# MCU_power_input.net
KiCad netlist of a schematic drawn in Altium Designer
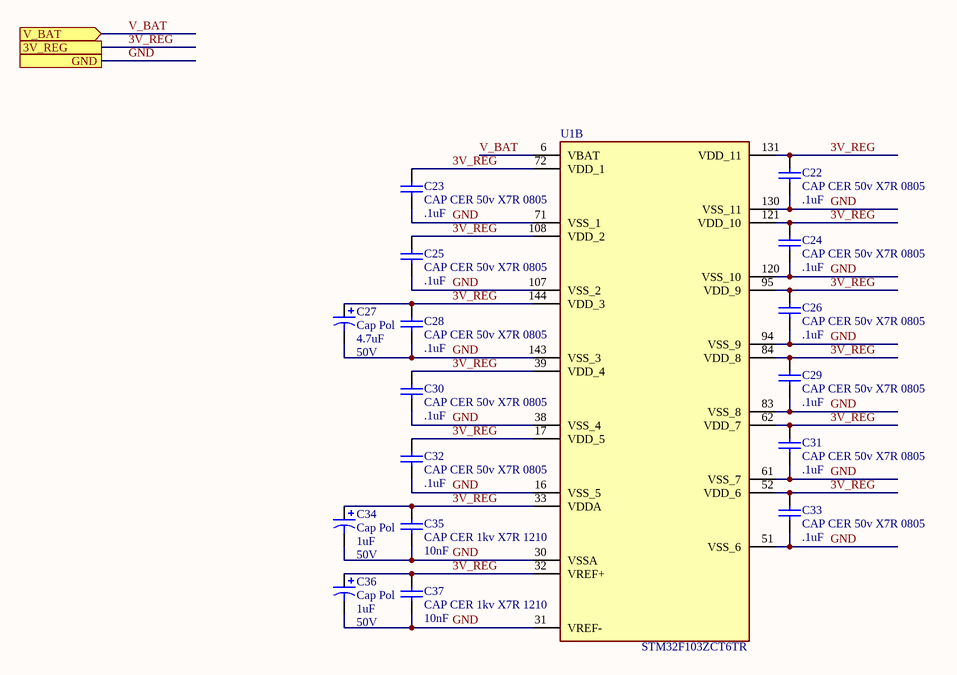
[diagram p0: MCU_power_input.SchDoc]

(export (version "E")
  (design (tool "Eeschema 10.0.6"))
  (components
    (comp (ref "C22")
      (value "CAP CER 50v X7R 0805")
      (footprint "CAPC2012X09M")
      (fields
        (field (name "ALTIUM_VALUE") ".1uF")
        (field (name "TOLERANCE") "±5%")
        (field (name "MPN") "C0805C104J5RACTU")
      )
      (libsource (lib "esd_library") (part "CAP-X7R-.1uF-50V-±5%"))
    )
    (comp (ref "C23")
      (value "CAP CER 50v X7R 0805")
      (footprint "CAPC2012X09M")
      (fields
        (field (name "ALTIUM_VALUE") ".1uF")
        (field (name "TOLERANCE") "±5%")
        (field (name "MPN") "C0805C104J5RACTU")
      )
      (libsource (lib "esd_library") (part "CAP-X7R-.1uF-50V-±5%"))
    )
    (comp (ref "C24")
      (value "CAP CER 50v X7R 0805")
      (footprint "CAPC2012X09M")
      (fields
        (field (name "ALTIUM_VALUE") ".1uF")
        (field (name "TOLERANCE") "±5%")
        (field (name "MPN") "C0805C104J5RACTU")
      )
      (libsource (lib "esd_library") (part "CAP-X7R-.1uF-50V-±5%"))
    )
    (comp (ref "C25")
      (value "CAP CER 50v X7R 0805")
      (footprint "CAPC2012X09M")
      (fields
        (field (name "ALTIUM_VALUE") ".1uF")
        (field (name "TOLERANCE") "±5%")
        (field (name "MPN") "C0805C104J5RACTU")
      )
      (libsource (lib "esd_library") (part "CAP-X7R-.1uF-50V-±5%"))
    )
    (comp (ref "C26")
      (value "CAP CER 50v X7R 0805")
      (footprint "CAPC2012X09M")
      (fields
        (field (name "ALTIUM_VALUE") ".1uF")
        (field (name "TOLERANCE") "±5%")
        (field (name "MPN") "C0805C104J5RACTU")
      )
      (libsource (lib "esd_library") (part "CAP-X7R-.1uF-50V-±5%"))
    )
    (comp (ref "C27")
      (value "Cap Pol")
      (footprint "CAPACITOR_5MM")
      (description "CAP 85C 4.7uF ±20% 50V WX Series Aluminum Electrolytic")
      (fields
        (field (name "ALTIUM_VALUE") "4.7uF")
        (field (name "VOLTAGE") "50V")
        (field (name "MPN") "UWX1H4R7MCL1GB")
      )
      (libsource (lib "esd_library") (part "Cap Polar-4.7uF-50V"))
    )
    (comp (ref "C28")
      (value "CAP CER 50v X7R 0805")
      (footprint "CAPC2012X09M")
      (fields
        (field (name "ALTIUM_VALUE") ".1uF")
        (field (name "TOLERANCE") "±5%")
        (field (name "MPN") "C0805C104J5RACTU")
      )
      (libsource (lib "esd_library") (part "CAP-X7R-.1uF-50V-±5%"))
    )
    (comp (ref "C29")
      (value "CAP CER 50v X7R 0805")
      (footprint "CAPC2012X09M")
      (fields
        (field (name "ALTIUM_VALUE") ".1uF")
        (field (name "TOLERANCE") "±5%")
        (field (name "MPN") "C0805C104J5RACTU")
      )
      (libsource (lib "esd_library") (part "CAP-X7R-.1uF-50V-±5%"))
    )
    (comp (ref "C30")
      (value "CAP CER 50v X7R 0805")
      (footprint "CAPC2012X09M")
      (fields
        (field (name "ALTIUM_VALUE") ".1uF")
        (field (name "TOLERANCE") "±5%")
        (field (name "MPN") "C0805C104J5RACTU")
      )
      (libsource (lib "esd_library") (part "CAP-X7R-.1uF-50V-±5%"))
    )
    (comp (ref "C31")
      (value "CAP CER 50v X7R 0805")
      (footprint "CAPC2012X09M")
      (fields
        (field (name "ALTIUM_VALUE") ".1uF")
        (field (name "TOLERANCE") "±5%")
        (field (name "MPN") "C0805C104J5RACTU")
      )
      (libsource (lib "esd_library") (part "CAP-X7R-.1uF-50V-±5%"))
    )
    (comp (ref "C32")
      (value "CAP CER 50v X7R 0805")
      (footprint "CAPC2012X09M")
      (fields
        (field (name "ALTIUM_VALUE") ".1uF")
        (field (name "TOLERANCE") "±5%")
        (field (name "MPN") "C0805C104J5RACTU")
      )
      (libsource (lib "esd_library") (part "CAP-X7R-.1uF-50V-±5%"))
    )
    (comp (ref "C33")
      (value "CAP CER 50v X7R 0805")
      (footprint "CAPC2012X09M")
      (fields
        (field (name "ALTIUM_VALUE") ".1uF")
        (field (name "TOLERANCE") "±5%")
        (field (name "MPN") "C0805C104J5RACTU")
      )
      (libsource (lib "esd_library") (part "CAP-X7R-.1uF-50V-±5%"))
    )
    (comp (ref "C34")
      (value "Cap Pol")
      (footprint "CAPACITOR_3MM")
      (description "CAP 85C 1uF ±20% 50V WX Series Aluminum Electrolytic")
      (fields
        (field (name "ALTIUM_VALUE") "1uF")
        (field (name "VOLTAGE") "50V")
        (field (name "MPN") "UWX1H010MCL2GB")
      )
      (libsource (lib "esd_library") (part "Cap Polar-1uF-50V"))
    )
    (comp (ref "C35")
      (value "CAP CER 1kv X7R 1210")
      (footprint "CAPC3225X25M")
      (fields
        (field (name "ALTIUM_VALUE") "10nF")
        (field (name "TOLERANCE") "±5%")
        (field (name "MPN") "C1210C103JDRACTU")
      )
      (libsource (lib "esd_library") (part "CAP-X7R-10000pF-1000V-±5%"))
    )
    (comp (ref "C36")
      (value "Cap Pol")
      (footprint "CAPACITOR_3MM")
      (description "CAP 85C 1uF ±20% 50V WX Series Aluminum Electrolytic")
      (fields
        (field (name "ALTIUM_VALUE") "1uF")
        (field (name "VOLTAGE") "50V")
        (field (name "MPN") "UWX1H010MCL2GB")
      )
      (libsource (lib "esd_library") (part "Cap Polar-1uF-50V"))
    )
    (comp (ref "C37")
      (value "CAP CER 1kv X7R 1210")
      (footprint "CAPC3225X25M")
      (fields
        (field (name "ALTIUM_VALUE") "10nF")
        (field (name "TOLERANCE") "±5%")
        (field (name "MPN") "C1210C103JDRACTU")
      )
      (libsource (lib "esd_library") (part "CAP-X7R-10000pF-1000V-±5%"))
    )
    (comp (ref "U1")
      (value "STM32F103ZCT6TR")
      (footprint "QFP50P2200X2200X160-144N")
      (fields (field (name "DIGI-KEY_PART_NUMBER") "497-18761-2-ND") (field (name "MF") "STMicroelectronics"))
      (libsource (lib "STM32F103ZCT6TR") (part "STM32F103ZCT6TR"))
    )
  )
  (nets
    (net (code "1") (name "/3V_REG") (class "Default")
      (node (ref "C22") (pin "2") (pinfunction "2_2") (pintype "passive"))
      (node (ref "C23") (pin "2") (pinfunction "2_2") (pintype "passive"))
      (node (ref "C24") (pin "2") (pinfunction "2_2") (pintype "passive"))
      (node (ref "C25") (pin "2") (pinfunction "2_2") (pintype "passive"))
      (node (ref "C26") (pin "2") (pinfunction "2_2") (pintype "passive"))
      (node (ref "C27") (pin "1") (pinfunction "1_1") (pintype "passive"))
      (node (ref "C28") (pin "2") (pinfunction "2_2") (pintype "passive"))
      (node (ref "C29") (pin "2") (pinfunction "2_2") (pintype "passive"))
      (node (ref "C30") (pin "2") (pinfunction "2_2") (pintype "passive"))
      (node (ref "C31") (pin "2") (pinfunction "2_2") (pintype "passive"))
      (node (ref "C32") (pin "2") (pinfunction "2_2") (pintype "passive"))
      (node (ref "C33") (pin "2") (pinfunction "2_2") (pintype "passive"))
      (node (ref "C34") (pin "1") (pinfunction "1_1") (pintype "passive"))
      (node (ref "C35") (pin "2") (pinfunction "2_2") (pintype "passive"))
      (node (ref "C36") (pin "1") (pinfunction "1_1") (pintype "passive"))
      (node (ref "C37") (pin "2") (pinfunction "2_2") (pintype "passive"))
      (node (ref "U1") (pin "108") (pinfunction "VDD_2_108") (pintype "power_in"))
      (node (ref "U1") (pin "121") (pinfunction "VDD_10_121") (pintype "power_in"))
      (node (ref "U1") (pin "131") (pinfunction "VDD_11_131") (pintype "power_in"))
      (node (ref "U1") (pin "144") (pinfunction "VDD_3_144") (pintype "power_in"))
      (node (ref "U1") (pin "17") (pinfunction "VDD_5_17") (pintype "power_in"))
      (node (ref "U1") (pin "32") (pinfunction "VREF+_32") (pintype "power_in"))
      (node (ref "U1") (pin "33") (pinfunction "VDDA_33") (pintype "power_in"))
      (node (ref "U1") (pin "39") (pinfunction "VDD_4_39") (pintype "power_in"))
      (node (ref "U1") (pin "52") (pinfunction "VDD_6_52") (pintype "power_in"))
      (node (ref "U1") (pin "62") (pinfunction "VDD_7_62") (pintype "power_in"))
      (node (ref "U1") (pin "72") (pinfunction "VDD_1_72") (pintype "power_in"))
      (node (ref "U1") (pin "84") (pinfunction "VDD_8_84") (pintype "power_in"))
      (node (ref "U1") (pin "95") (pinfunction "VDD_9_95") (pintype "power_in"))
    )
    (net (code "2") (name "/GND") (class "Default")
      (node (ref "C22") (pin "1") (pinfunction "1_1") (pintype "passive"))
      (node (ref "C23") (pin "1") (pinfunction "1_1") (pintype "passive"))
      (node (ref "C24") (pin "1") (pinfunction "1_1") (pintype "passive"))
      (node (ref "C25") (pin "1") (pinfunction "1_1") (pintype "passive"))
      (node (ref "C26") (pin "1") (pinfunction "1_1") (pintype "passive"))
      (node (ref "C27") (pin "2") (pinfunction "2_2") (pintype "passive"))
      (node (ref "C28") (pin "1") (pinfunction "1_1") (pintype "passive"))
      (node (ref "C29") (pin "1") (pinfunction "1_1") (pintype "passive"))
      (node (ref "C30") (pin "1") (pinfunction "1_1") (pintype "passive"))
      (node (ref "C31") (pin "1") (pinfunction "1_1") (pintype "passive"))
      (node (ref "C32") (pin "1") (pinfunction "1_1") (pintype "passive"))
      (node (ref "C33") (pin "1") (pinfunction "1_1") (pintype "passive"))
      (node (ref "C34") (pin "2") (pinfunction "2_2") (pintype "passive"))
      (node (ref "C35") (pin "1") (pinfunction "1_1") (pintype "passive"))
      (node (ref "C36") (pin "2") (pinfunction "2_2") (pintype "passive"))
      (node (ref "C37") (pin "1") (pinfunction "1_1") (pintype "passive"))
      (node (ref "U1") (pin "107") (pinfunction "VSS_2_107") (pintype "power_in"))
      (node (ref "U1") (pin "120") (pinfunction "VSS_10_120") (pintype "power_in"))
      (node (ref "U1") (pin "130") (pinfunction "VSS_11_130") (pintype "power_in"))
      (node (ref "U1") (pin "143") (pinfunction "VSS_3_143") (pintype "power_in"))
      (node (ref "U1") (pin "16") (pinfunction "VSS_5_16") (pintype "power_in"))
      (node (ref "U1") (pin "30") (pinfunction "VSSA_30") (pintype "power_in"))
      (node (ref "U1") (pin "31") (pinfunction "VREF-_31") (pintype "power_in"))
      (node (ref "U1") (pin "38") (pinfunction "VSS_4_38") (pintype "power_in"))
      (node (ref "U1") (pin "51") (pinfunction "VSS_6_51") (pintype "power_in"))
      (node (ref "U1") (pin "61") (pinfunction "VSS_7_61") (pintype "power_in"))
      (node (ref "U1") (pin "71") (pinfunction "VSS_1_71") (pintype "power_in"))
      (node (ref "U1") (pin "83") (pinfunction "VSS_8_83") (pintype "power_in"))
      (node (ref "U1") (pin "94") (pinfunction "VSS_9_94") (pintype "power_in"))
    )
    (net (code "3") (name "/V_BAT") (class "Default")
      (node (ref "U1") (pin "6") (pinfunction "VBAT_6") (pintype "power_in"))
    )
  )
)
